# Adapter.net
KiCad netlist of a schematic drawn in Altium Designer
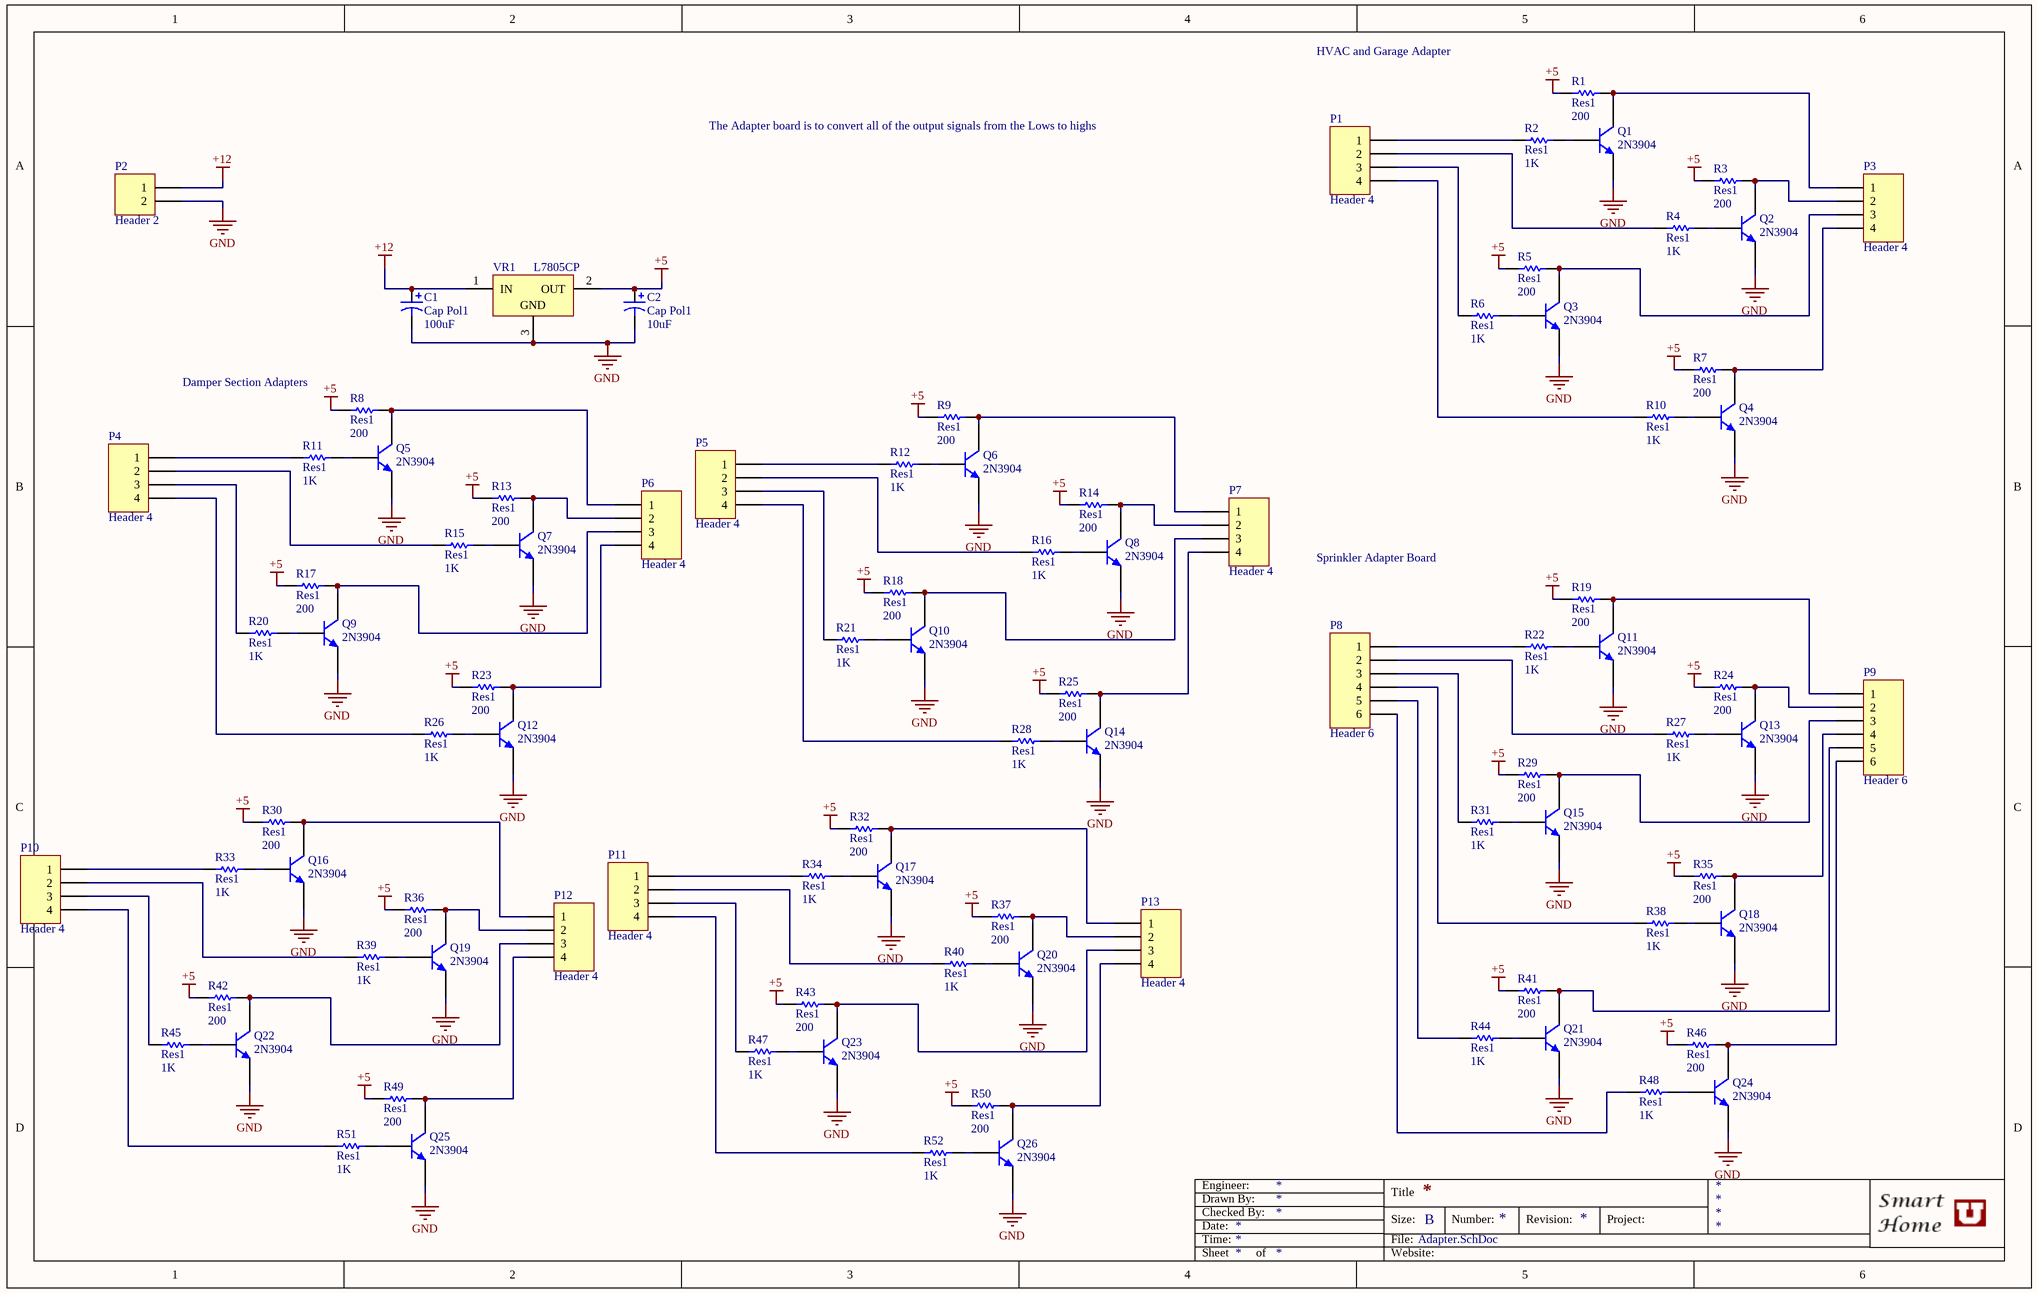
[diagram p0: Adapter.SchDoc]

(export (version "E")
  (design (tool "Eeschema 10.0.6"))
  (components
    (comp (ref "C1")
      (value "Cap Pol1")
      (footprint "RB7.6-15")
      (description "Polarized Capacitor (Radial)")
      (fields (field (name "ALTIUM_VALUE") "100uF") (field (name "PUBLISHER") "Altium Limited"))
      (libsource (lib "Miscellaneous Devices") (part "Cap Pol1"))
    )
    (comp (ref "C2")
      (value "Cap Pol1")
      (footprint "RB7.6-15")
      (description "Polarized Capacitor (Radial)")
      (fields (field (name "ALTIUM_VALUE") "10uF") (field (name "PUBLISHER") "Altium Limited"))
      (libsource (lib "Miscellaneous Devices") (part "Cap Pol1"))
    )
    (comp (ref "P1")
      (value "Header 4")
      (footprint "HDR1X4")
      (description "Header, 4-Pin")
      (fields (field (name "PUBLISHER") "Altium Limited"))
      (libsource (lib "") (part "Header 4_1"))
    )
    (comp (ref "P2")
      (value "Header 2")
      (footprint "HDR1X2")
      (description "Header, 2-Pin")
      (fields (field (name "PUBLISHER") "Altium Limited"))
      (libsource (lib "Miscellaneous Connectors") (part "Header 2"))
    )
    (comp (ref "P3")
      (value "Header 4")
      (footprint "HDR1X4")
      (description "Header, 4-Pin")
      (fields (field (name "PUBLISHER") "Altium Limited"))
      (libsource (lib "Miscellaneous Connectors") (part "Header 4"))
    )
    (comp (ref "P4")
      (value "Header 4")
      (footprint "HDR1X4")
      (description "Header, 4-Pin")
      (fields (field (name "PUBLISHER") "Altium Limited"))
      (libsource (lib "") (part "Header 4_1"))
    )
    (comp (ref "P5")
      (value "Header 4")
      (footprint "HDR1X4")
      (description "Header, 4-Pin")
      (fields (field (name "PUBLISHER") "Altium Limited"))
      (libsource (lib "") (part "Header 4_1"))
    )
    (comp (ref "P6")
      (value "Header 4")
      (footprint "HDR1X4")
      (description "Header, 4-Pin")
      (fields (field (name "PUBLISHER") "Altium Limited"))
      (libsource (lib "Miscellaneous Connectors") (part "Header 4"))
    )
    (comp (ref "P7")
      (value "Header 4")
      (footprint "HDR1X4")
      (description "Header, 4-Pin")
      (fields (field (name "PUBLISHER") "Altium Limited"))
      (libsource (lib "Miscellaneous Connectors") (part "Header 4"))
    )
    (comp (ref "P8")
      (value "Header 6")
      (footprint "HDR1X6")
      (description "Header, 6-Pin")
      (fields (field (name "PUBLISHER") "Altium Limited"))
      (libsource (lib "Miscellaneous Connectors") (part "Header 6"))
    )
    (comp (ref "P9")
      (value "Header 6")
      (footprint "HDR1X6")
      (description "Header, 6-Pin")
      (fields (field (name "PUBLISHER") "Altium Limited"))
      (libsource (lib "") (part "Header 6_1"))
    )
    (comp (ref "P10")
      (value "Header 4")
      (footprint "HDR1X4")
      (description "Header, 4-Pin")
      (fields (field (name "PUBLISHER") "Altium Limited"))
      (libsource (lib "") (part "Header 4_1"))
    )
    (comp (ref "P11")
      (value "Header 4")
      (footprint "HDR1X4")
      (description "Header, 4-Pin")
      (fields (field (name "PUBLISHER") "Altium Limited"))
      (libsource (lib "") (part "Header 4_1"))
    )
    (comp (ref "P12")
      (value "Header 4")
      (footprint "HDR1X4")
      (description "Header, 4-Pin")
      (fields (field (name "PUBLISHER") "Altium Limited"))
      (libsource (lib "Miscellaneous Connectors") (part "Header 4"))
    )
    (comp (ref "P13")
      (value "Header 4")
      (footprint "HDR1X4")
      (description "Header, 4-Pin")
      (fields (field (name "PUBLISHER") "Altium Limited"))
      (libsource (lib "Miscellaneous Connectors") (part "Header 4"))
    )
    (comp (ref "Q1")
      (value "2N3904")
      (footprint "2N3904")
      (description "NPN General Purpose Amplifier")
      (fields (field (name "PUBLISHER") "Altium Limited"))
      (libsource (lib "Miscellaneous Devices") (part "2N3904"))
    )
    (comp (ref "Q2")
      (value "2N3904")
      (footprint "2N3904")
      (description "NPN General Purpose Amplifier")
      (fields (field (name "PUBLISHER") "Altium Limited"))
      (libsource (lib "Miscellaneous Devices") (part "2N3904"))
    )
    (comp (ref "Q3")
      (value "2N3904")
      (footprint "2N3904")
      (description "NPN General Purpose Amplifier")
      (fields (field (name "PUBLISHER") "Altium Limited"))
      (libsource (lib "Miscellaneous Devices") (part "2N3904"))
    )
    (comp (ref "Q4")
      (value "2N3904")
      (footprint "2N3904")
      (description "NPN General Purpose Amplifier")
      (fields (field (name "PUBLISHER") "Altium Limited"))
      (libsource (lib "Miscellaneous Devices") (part "2N3904"))
    )
    (comp (ref "Q5")
      (value "2N3904")
      (footprint "2N3904")
      (description "NPN General Purpose Amplifier")
      (fields (field (name "PUBLISHER") "Altium Limited"))
      (libsource (lib "Miscellaneous Devices") (part "2N3904"))
    )
    (comp (ref "Q6")
      (value "2N3904")
      (footprint "2N3904")
      (description "NPN General Purpose Amplifier")
      (fields (field (name "PUBLISHER") "Altium Limited"))
      (libsource (lib "Miscellaneous Devices") (part "2N3904"))
    )
    (comp (ref "Q7")
      (value "2N3904")
      (footprint "2N3904")
      (description "NPN General Purpose Amplifier")
      (fields (field (name "PUBLISHER") "Altium Limited"))
      (libsource (lib "Miscellaneous Devices") (part "2N3904"))
    )
    (comp (ref "Q8")
      (value "2N3904")
      (footprint "2N3904")
      (description "NPN General Purpose Amplifier")
      (fields (field (name "PUBLISHER") "Altium Limited"))
      (libsource (lib "Miscellaneous Devices") (part "2N3904"))
    )
    (comp (ref "Q9")
      (value "2N3904")
      (footprint "2N3904")
      (description "NPN General Purpose Amplifier")
      (fields (field (name "PUBLISHER") "Altium Limited"))
      (libsource (lib "Miscellaneous Devices") (part "2N3904"))
    )
    (comp (ref "Q10")
      (value "2N3904")
      (footprint "2N3904")
      (description "NPN General Purpose Amplifier")
      (fields (field (name "PUBLISHER") "Altium Limited"))
      (libsource (lib "Miscellaneous Devices") (part "2N3904"))
    )
    (comp (ref "Q11")
      (value "2N3904")
      (footprint "2N3904")
      (description "NPN General Purpose Amplifier")
      (fields (field (name "PUBLISHER") "Altium Limited"))
      (libsource (lib "Miscellaneous Devices") (part "2N3904"))
    )
    (comp (ref "Q12")
      (value "2N3904")
      (footprint "2N3904")
      (description "NPN General Purpose Amplifier")
      (fields (field (name "PUBLISHER") "Altium Limited"))
      (libsource (lib "Miscellaneous Devices") (part "2N3904"))
    )
    (comp (ref "Q13")
      (value "2N3904")
      (footprint "2N3904")
      (description "NPN General Purpose Amplifier")
      (fields (field (name "PUBLISHER") "Altium Limited"))
      (libsource (lib "Miscellaneous Devices") (part "2N3904"))
    )
    (comp (ref "Q14")
      (value "2N3904")
      (footprint "2N3904")
      (description "NPN General Purpose Amplifier")
      (fields (field (name "PUBLISHER") "Altium Limited"))
      (libsource (lib "Miscellaneous Devices") (part "2N3904"))
    )
    (comp (ref "Q15")
      (value "2N3904")
      (footprint "2N3904")
      (description "NPN General Purpose Amplifier")
      (fields (field (name "PUBLISHER") "Altium Limited"))
      (libsource (lib "Miscellaneous Devices") (part "2N3904"))
    )
    (comp (ref "Q16")
      (value "2N3904")
      (footprint "2N3904")
      (description "NPN General Purpose Amplifier")
      (fields (field (name "PUBLISHER") "Altium Limited"))
      (libsource (lib "Miscellaneous Devices") (part "2N3904"))
    )
    (comp (ref "Q17")
      (value "2N3904")
      (footprint "2N3904")
      (description "NPN General Purpose Amplifier")
      (fields (field (name "PUBLISHER") "Altium Limited"))
      (libsource (lib "Miscellaneous Devices") (part "2N3904"))
    )
    (comp (ref "Q18")
      (value "2N3904")
      (footprint "2N3904")
      (description "NPN General Purpose Amplifier")
      (fields (field (name "PUBLISHER") "Altium Limited"))
      (libsource (lib "Miscellaneous Devices") (part "2N3904"))
    )
    (comp (ref "Q19")
      (value "2N3904")
      (footprint "2N3904")
      (description "NPN General Purpose Amplifier")
      (fields (field (name "PUBLISHER") "Altium Limited"))
      (libsource (lib "Miscellaneous Devices") (part "2N3904"))
    )
    (comp (ref "Q20")
      (value "2N3904")
      (footprint "2N3904")
      (description "NPN General Purpose Amplifier")
      (fields (field (name "PUBLISHER") "Altium Limited"))
      (libsource (lib "Miscellaneous Devices") (part "2N3904"))
    )
    (comp (ref "Q21")
      (value "2N3904")
      (footprint "2N3904")
      (description "NPN General Purpose Amplifier")
      (fields (field (name "PUBLISHER") "Altium Limited"))
      (libsource (lib "Miscellaneous Devices") (part "2N3904"))
    )
    (comp (ref "Q22")
      (value "2N3904")
      (footprint "2N3904")
      (description "NPN General Purpose Amplifier")
      (fields (field (name "PUBLISHER") "Altium Limited"))
      (libsource (lib "Miscellaneous Devices") (part "2N3904"))
    )
    (comp (ref "Q23")
      (value "2N3904")
      (footprint "2N3904")
      (description "NPN General Purpose Amplifier")
      (fields (field (name "PUBLISHER") "Altium Limited"))
      (libsource (lib "Miscellaneous Devices") (part "2N3904"))
    )
    (comp (ref "Q24")
      (value "2N3904")
      (footprint "2N3904")
      (description "NPN General Purpose Amplifier")
      (fields (field (name "PUBLISHER") "Altium Limited"))
      (libsource (lib "Miscellaneous Devices") (part "2N3904"))
    )
    (comp (ref "Q25")
      (value "2N3904")
      (footprint "2N3904")
      (description "NPN General Purpose Amplifier")
      (fields (field (name "PUBLISHER") "Altium Limited"))
      (libsource (lib "Miscellaneous Devices") (part "2N3904"))
    )
    (comp (ref "Q26")
      (value "2N3904")
      (footprint "2N3904")
      (description "NPN General Purpose Amplifier")
      (fields (field (name "PUBLISHER") "Altium Limited"))
      (libsource (lib "Miscellaneous Devices") (part "2N3904"))
    )
    (comp (ref "R1")
      (value "Res1")
      (footprint "AXIAL-0.3")
      (description "Resistor")
      (fields (field (name "ALTIUM_VALUE") "200") (field (name "PUBLISHER") "Altium Limited"))
      (libsource (lib "Miscellaneous Devices") (part "Res1"))
    )
    (comp (ref "R2")
      (value "Res1")
      (footprint "AXIAL-0.3")
      (description "Resistor")
      (fields (field (name "ALTIUM_VALUE") "1K") (field (name "PUBLISHER") "Altium Limited"))
      (libsource (lib "Miscellaneous Devices") (part "Res1"))
    )
    (comp (ref "R3")
      (value "Res1")
      (footprint "AXIAL-0.3")
      (description "Resistor")
      (fields (field (name "ALTIUM_VALUE") "200") (field (name "PUBLISHER") "Altium Limited"))
      (libsource (lib "Miscellaneous Devices") (part "Res1"))
    )
    (comp (ref "R4")
      (value "Res1")
      (footprint "AXIAL-0.3")
      (description "Resistor")
      (fields (field (name "ALTIUM_VALUE") "1K") (field (name "PUBLISHER") "Altium Limited"))
      (libsource (lib "Miscellaneous Devices") (part "Res1"))
    )
    (comp (ref "R5")
      (value "Res1")
      (footprint "AXIAL-0.3")
      (description "Resistor")
      (fields (field (name "ALTIUM_VALUE") "200") (field (name "PUBLISHER") "Altium Limited"))
      (libsource (lib "Miscellaneous Devices") (part "Res1"))
    )
    (comp (ref "R6")
      (value "Res1")
      (footprint "AXIAL-0.3")
      (description "Resistor")
      (fields (field (name "ALTIUM_VALUE") "1K") (field (name "PUBLISHER") "Altium Limited"))
      (libsource (lib "Miscellaneous Devices") (part "Res1"))
    )
    (comp (ref "R7")
      (value "Res1")
      (footprint "AXIAL-0.3")
      (description "Resistor")
      (fields (field (name "ALTIUM_VALUE") "200") (field (name "PUBLISHER") "Altium Limited"))
      (libsource (lib "Miscellaneous Devices") (part "Res1"))
    )
    (comp (ref "R8")
      (value "Res1")
      (footprint "AXIAL-0.3")
      (description "Resistor")
      (fields (field (name "ALTIUM_VALUE") "200") (field (name "PUBLISHER") "Altium Limited"))
      (libsource (lib "Miscellaneous Devices") (part "Res1"))
    )
    (comp (ref "R9")
      (value "Res1")
      (footprint "AXIAL-0.3")
      (description "Resistor")
      (fields (field (name "ALTIUM_VALUE") "200") (field (name "PUBLISHER") "Altium Limited"))
      (libsource (lib "Miscellaneous Devices") (part "Res1"))
    )
    (comp (ref "R10")
      (value "Res1")
      (footprint "AXIAL-0.3")
      (description "Resistor")
      (fields (field (name "ALTIUM_VALUE") "1K") (field (name "PUBLISHER") "Altium Limited"))
      (libsource (lib "Miscellaneous Devices") (part "Res1"))
    )
    (comp (ref "R11")
      (value "Res1")
      (footprint "AXIAL-0.3")
      (description "Resistor")
      (fields (field (name "ALTIUM_VALUE") "1K") (field (name "PUBLISHER") "Altium Limited"))
      (libsource (lib "Miscellaneous Devices") (part "Res1"))
    )
    (comp (ref "R12")
      (value "Res1")
      (footprint "AXIAL-0.3")
      (description "Resistor")
      (fields (field (name "ALTIUM_VALUE") "1K") (field (name "PUBLISHER") "Altium Limited"))
      (libsource (lib "Miscellaneous Devices") (part "Res1"))
    )
    (comp (ref "R13")
      (value "Res1")
      (footprint "AXIAL-0.3")
      (description "Resistor")
      (fields (field (name "ALTIUM_VALUE") "200") (field (name "PUBLISHER") "Altium Limited"))
      (libsource (lib "Miscellaneous Devices") (part "Res1"))
    )
    (comp (ref "R14")
      (value "Res1")
      (footprint "AXIAL-0.3")
      (description "Resistor")
      (fields (field (name "ALTIUM_VALUE") "200") (field (name "PUBLISHER") "Altium Limited"))
      (libsource (lib "Miscellaneous Devices") (part "Res1"))
    )
    (comp (ref "R15")
      (value "Res1")
      (footprint "AXIAL-0.3")
      (description "Resistor")
      (fields (field (name "ALTIUM_VALUE") "1K") (field (name "PUBLISHER") "Altium Limited"))
      (libsource (lib "Miscellaneous Devices") (part "Res1"))
    )
    (comp (ref "R16")
      (value "Res1")
      (footprint "AXIAL-0.3")
      (description "Resistor")
      (fields (field (name "ALTIUM_VALUE") "1K") (field (name "PUBLISHER") "Altium Limited"))
      (libsource (lib "Miscellaneous Devices") (part "Res1"))
    )
    (comp (ref "R17")
      (value "Res1")
      (footprint "AXIAL-0.3")
      (description "Resistor")
      (fields (field (name "ALTIUM_VALUE") "200") (field (name "PUBLISHER") "Altium Limited"))
      (libsource (lib "Miscellaneous Devices") (part "Res1"))
    )
    (comp (ref "R18")
      (value "Res1")
      (footprint "AXIAL-0.3")
      (description "Resistor")
      (fields (field (name "ALTIUM_VALUE") "200") (field (name "PUBLISHER") "Altium Limited"))
      (libsource (lib "Miscellaneous Devices") (part "Res1"))
    )
    (comp (ref "R19")
      (value "Res1")
      (footprint "AXIAL-0.3")
      (description "Resistor")
      (fields (field (name "ALTIUM_VALUE") "200") (field (name "PUBLISHER") "Altium Limited"))
      (libsource (lib "Miscellaneous Devices") (part "Res1"))
    )
    (comp (ref "R20")
      (value "Res1")
      (footprint "AXIAL-0.3")
      (description "Resistor")
      (fields (field (name "ALTIUM_VALUE") "1K") (field (name "PUBLISHER") "Altium Limited"))
      (libsource (lib "Miscellaneous Devices") (part "Res1"))
    )
    (comp (ref "R21")
      (value "Res1")
      (footprint "AXIAL-0.3")
      (description "Resistor")
      (fields (field (name "ALTIUM_VALUE") "1K") (field (name "PUBLISHER") "Altium Limited"))
      (libsource (lib "Miscellaneous Devices") (part "Res1"))
    )
    (comp (ref "R22")
      (value "Res1")
      (footprint "AXIAL-0.3")
      (description "Resistor")
      (fields (field (name "ALTIUM_VALUE") "1K") (field (name "PUBLISHER") "Altium Limited"))
      (libsource (lib "Miscellaneous Devices") (part "Res1"))
    )
    (comp (ref "R23")
      (value "Res1")
      (footprint "AXIAL-0.3")
      (description "Resistor")
      (fields (field (name "ALTIUM_VALUE") "200") (field (name "PUBLISHER") "Altium Limited"))
      (libsource (lib "Miscellaneous Devices") (part "Res1"))
    )
    (comp (ref "R24")
      (value "Res1")
      (footprint "AXIAL-0.3")
      (description "Resistor")
      (fields (field (name "ALTIUM_VALUE") "200") (field (name "PUBLISHER") "Altium Limited"))
      (libsource (lib "Miscellaneous Devices") (part "Res1"))
    )
    (comp (ref "R25")
      (value "Res1")
      (footprint "AXIAL-0.3")
      (description "Resistor")
      (fields (field (name "ALTIUM_VALUE") "200") (field (name "PUBLISHER") "Altium Limited"))
      (libsource (lib "Miscellaneous Devices") (part "Res1"))
    )
    (comp (ref "R26")
      (value "Res1")
      (footprint "AXIAL-0.3")
      (description "Resistor")
      (fields (field (name "ALTIUM_VALUE") "1K") (field (name "PUBLISHER") "Altium Limited"))
      (libsource (lib "Miscellaneous Devices") (part "Res1"))
    )
    (comp (ref "R27")
      (value "Res1")
      (footprint "AXIAL-0.3")
      (description "Resistor")
      (fields (field (name "ALTIUM_VALUE") "1K") (field (name "PUBLISHER") "Altium Limited"))
      (libsource (lib "Miscellaneous Devices") (part "Res1"))
    )
    (comp (ref "R28")
      (value "Res1")
      (footprint "AXIAL-0.3")
      (description "Resistor")
      (fields (field (name "ALTIUM_VALUE") "1K") (field (name "PUBLISHER") "Altium Limited"))
      (libsource (lib "Miscellaneous Devices") (part "Res1"))
    )
    (comp (ref "R29")
      (value "Res1")
      (footprint "AXIAL-0.3")
      (description "Resistor")
      (fields (field (name "ALTIUM_VALUE") "200") (field (name "PUBLISHER") "Altium Limited"))
      (libsource (lib "Miscellaneous Devices") (part "Res1"))
    )
    (comp (ref "R30")
      (value "Res1")
      (footprint "AXIAL-0.3")
      (description "Resistor")
      (fields (field (name "ALTIUM_VALUE") "200") (field (name "PUBLISHER") "Altium Limited"))
      (libsource (lib "Miscellaneous Devices") (part "Res1"))
    )
    (comp (ref "R31")
      (value "Res1")
      (footprint "AXIAL-0.3")
      (description "Resistor")
      (fields (field (name "ALTIUM_VALUE") "1K") (field (name "PUBLISHER") "Altium Limited"))
      (libsource (lib "Miscellaneous Devices") (part "Res1"))
    )
    (comp (ref "R32")
      (value "Res1")
      (footprint "AXIAL-0.3")
      (description "Resistor")
      (fields (field (name "ALTIUM_VALUE") "200") (field (name "PUBLISHER") "Altium Limited"))
      (libsource (lib "Miscellaneous Devices") (part "Res1"))
    )
    (comp (ref "R33")
      (value "Res1")
      (footprint "AXIAL-0.3")
      (description "Resistor")
      (fields (field (name "ALTIUM_VALUE") "1K") (field (name "PUBLISHER") "Altium Limited"))
      (libsource (lib "Miscellaneous Devices") (part "Res1"))
    )
    (comp (ref "R34")
      (value "Res1")
      (footprint "AXIAL-0.3")
      (description "Resistor")
      (fields (field (name "ALTIUM_VALUE") "1K") (field (name "PUBLISHER") "Altium Limited"))
      (libsource (lib "Miscellaneous Devices") (part "Res1"))
    )
    (comp (ref "R35")
      (value "Res1")
      (footprint "AXIAL-0.3")
      (description "Resistor")
      (fields (field (name "ALTIUM_VALUE") "200") (field (name "PUBLISHER") "Altium Limited"))
      (libsource (lib "Miscellaneous Devices") (part "Res1"))
    )
    (comp (ref "R36")
      (value "Res1")
      (footprint "AXIAL-0.3")
      (description "Resistor")
      (fields (field (name "ALTIUM_VALUE") "200") (field (name "PUBLISHER") "Altium Limited"))
      (libsource (lib "Miscellaneous Devices") (part "Res1"))
    )
    (comp (ref "R37")
      (value "Res1")
      (footprint "AXIAL-0.3")
      (description "Resistor")
      (fields (field (name "ALTIUM_VALUE") "200") (field (name "PUBLISHER") "Altium Limited"))
      (libsource (lib "Miscellaneous Devices") (part "Res1"))
    )
    (comp (ref "R38")
      (value "Res1")
      (footprint "AXIAL-0.3")
      (description "Resistor")
      (fields (field (name "ALTIUM_VALUE") "1K") (field (name "PUBLISHER") "Altium Limited"))
      (libsource (lib "Miscellaneous Devices") (part "Res1"))
    )
    (comp (ref "R39")
      (value "Res1")
      (footprint "AXIAL-0.3")
      (description "Resistor")
      (fields (field (name "ALTIUM_VALUE") "1K") (field (name "PUBLISHER") "Altium Limited"))
      (libsource (lib "Miscellaneous Devices") (part "Res1"))
    )
    (comp (ref "R40")
      (value "Res1")
      (footprint "AXIAL-0.3")
      (description "Resistor")
      (fields (field (name "ALTIUM_VALUE") "1K") (field (name "PUBLISHER") "Altium Limited"))
      (libsource (lib "Miscellaneous Devices") (part "Res1"))
    )
    (comp (ref "R41")
      (value "Res1")
      (footprint "AXIAL-0.3")
      (description "Resistor")
      (fields (field (name "ALTIUM_VALUE") "200") (field (name "PUBLISHER") "Altium Limited"))
      (libsource (lib "Miscellaneous Devices") (part "Res1"))
    )
    (comp (ref "R42")
      (value "Res1")
      (footprint "AXIAL-0.3")
      (description "Resistor")
      (fields (field (name "ALTIUM_VALUE") "200") (field (name "PUBLISHER") "Altium Limited"))
      (libsource (lib "Miscellaneous Devices") (part "Res1"))
    )
    (comp (ref "R43")
      (value "Res1")
      (footprint "AXIAL-0.3")
      (description "Resistor")
      (fields (field (name "ALTIUM_VALUE") "200") (field (name "PUBLISHER") "Altium Limited"))
      (libsource (lib "Miscellaneous Devices") (part "Res1"))
    )
    (comp (ref "R44")
      (value "Res1")
      (footprint "AXIAL-0.3")
      (description "Resistor")
      (fields (field (name "ALTIUM_VALUE") "1K") (field (name "PUBLISHER") "Altium Limited"))
      (libsource (lib "Miscellaneous Devices") (part "Res1"))
    )
    (comp (ref "R45")
      (value "Res1")
      (footprint "AXIAL-0.3")
      (description "Resistor")
      (fields (field (name "ALTIUM_VALUE") "1K") (field (name "PUBLISHER") "Altium Limited"))
      (libsource (lib "Miscellaneous Devices") (part "Res1"))
    )
    (comp (ref "R46")
      (value "Res1")
      (footprint "AXIAL-0.3")
      (description "Resistor")
      (fields (field (name "ALTIUM_VALUE") "200") (field (name "PUBLISHER") "Altium Limited"))
      (libsource (lib "Miscellaneous Devices") (part "Res1"))
    )
    (comp (ref "R47")
      (value "Res1")
      (footprint "AXIAL-0.3")
      (description "Resistor")
      (fields (field (name "ALTIUM_VALUE") "1K") (field (name "PUBLISHER") "Altium Limited"))
      (libsource (lib "Miscellaneous Devices") (part "Res1"))
    )
    (comp (ref "R48")
      (value "Res1")
      (footprint "AXIAL-0.3")
      (description "Resistor")
      (fields (field (name "ALTIUM_VALUE") "1K") (field (name "PUBLISHER") "Altium Limited"))
      (libsource (lib "Miscellaneous Devices") (part "Res1"))
    )
    (comp (ref "R49")
      (value "Res1")
      (footprint "AXIAL-0.3")
      (description "Resistor")
      (fields (field (name "ALTIUM_VALUE") "200") (field (name "PUBLISHER") "Altium Limited"))
      (libsource (lib "Miscellaneous Devices") (part "Res1"))
    )
    (comp (ref "R50")
      (value "Res1")
      (footprint "AXIAL-0.3")
      (description "Resistor")
      (fields (field (name "ALTIUM_VALUE") "200") (field (name "PUBLISHER") "Altium Limited"))
      (libsource (lib "Miscellaneous Devices") (part "Res1"))
    )
    (comp (ref "R51")
      (value "Res1")
      (footprint "AXIAL-0.3")
      (description "Resistor")
      (fields (field (name "ALTIUM_VALUE") "1K") (field (name "PUBLISHER") "Altium Limited"))
      (libsource (lib "Miscellaneous Devices") (part "Res1"))
    )
    (comp (ref "R52")
      (value "Res1")
      (footprint "AXIAL-0.3")
      (description "Resistor")
      (fields (field (name "ALTIUM_VALUE") "1K") (field (name "PUBLISHER") "Altium Limited"))
      (libsource (lib "Miscellaneous Devices") (part "Res1"))
    )
    (comp (ref "VR1")
      (value "L7805CP")
      (footprint "ISOWATT220AB")
      (description "Positive Voltage Regulator")
      (fields (field (name "PUBLISHER") "Altium Limited"))
      (libsource (lib "ST Power Mgt Voltage Regulator") (part "L7805CP"))
    )
  )
  (nets
    (net (code "1") (name "+5") (class "Default")
      (node (ref "C2") (pin "1") (pinfunction "1_1") (pintype "passive"))
      (node (ref "R1") (pin "1") (pinfunction "1_1") (pintype "passive"))
      (node (ref "R13") (pin "1") (pinfunction "1_1") (pintype "passive"))
      (node (ref "R14") (pin "1") (pinfunction "1_1") (pintype "passive"))
      (node (ref "R17") (pin "1") (pinfunction "1_1") (pintype "passive"))
      (node (ref "R18") (pin "1") (pinfunction "1_1") (pintype "passive"))
      (node (ref "R19") (pin "1") (pinfunction "1_1") (pintype "passive"))
      (node (ref "R23") (pin "1") (pinfunction "1_1") (pintype "passive"))
      (node (ref "R24") (pin "1") (pinfunction "1_1") (pintype "passive"))
      (node (ref "R25") (pin "1") (pinfunction "1_1") (pintype "passive"))
      (node (ref "R29") (pin "1") (pinfunction "1_1") (pintype "passive"))
      (node (ref "R3") (pin "1") (pinfunction "1_1") (pintype "passive"))
      (node (ref "R30") (pin "1") (pinfunction "1_1") (pintype "passive"))
      (node (ref "R32") (pin "1") (pinfunction "1_1") (pintype "passive"))
      (node (ref "R35") (pin "1") (pinfunction "1_1") (pintype "passive"))
      (node (ref "R36") (pin "1") (pinfunction "1_1") (pintype "passive"))
      (node (ref "R37") (pin "1") (pinfunction "1_1") (pintype "passive"))
      (node (ref "R41") (pin "1") (pinfunction "1_1") (pintype "passive"))
      (node (ref "R42") (pin "1") (pinfunction "1_1") (pintype "passive"))
      (node (ref "R43") (pin "1") (pinfunction "1_1") (pintype "passive"))
      (node (ref "R46") (pin "1") (pinfunction "1_1") (pintype "passive"))
      (node (ref "R49") (pin "1") (pinfunction "1_1") (pintype "passive"))
      (node (ref "R5") (pin "1") (pinfunction "1_1") (pintype "passive"))
      (node (ref "R50") (pin "1") (pinfunction "1_1") (pintype "passive"))
      (node (ref "R7") (pin "1") (pinfunction "1_1") (pintype "passive"))
      (node (ref "R8") (pin "1") (pinfunction "1_1") (pintype "passive"))
      (node (ref "R9") (pin "1") (pinfunction "1_1") (pintype "passive"))
      (node (ref "VR1") (pin "2") (pinfunction "OUT_2") (pintype "power_in"))
    )
    (net (code "2") (name "+12") (class "Default")
      (node (ref "C1") (pin "1") (pinfunction "1_1") (pintype "passive"))
      (node (ref "P2") (pin "1") (pinfunction "1_1") (pintype "passive"))
      (node (ref "VR1") (pin "1") (pinfunction "IN_1") (pintype "power_in"))
    )
    (net (code "3") (name "GND") (class "Default")
      (node (ref "C1") (pin "2") (pinfunction "2_2") (pintype "passive"))
      (node (ref "C2") (pin "2") (pinfunction "2_2") (pintype "passive"))
      (node (ref "P2") (pin "2") (pinfunction "2_2") (pintype "passive"))
      (node (ref "Q1") (pin "1") (pinfunction "E_1") (pintype "passive"))
      (node (ref "Q10") (pin "1") (pinfunction "E_1") (pintype "passive"))
      (node (ref "Q11") (pin "1") (pinfunction "E_1") (pintype "passive"))
      (node (ref "Q12") (pin "1") (pinfunction "E_1") (pintype "passive"))
      (node (ref "Q13") (pin "1") (pinfunction "E_1") (pintype "passive"))
      (node (ref "Q14") (pin "1") (pinfunction "E_1") (pintype "passive"))
      (node (ref "Q15") (pin "1") (pinfunction "E_1") (pintype "passive"))
      (node (ref "Q16") (pin "1") (pinfunction "E_1") (pintype "passive"))
      (node (ref "Q17") (pin "1") (pinfunction "E_1") (pintype "passive"))
      (node (ref "Q18") (pin "1") (pinfunction "E_1") (pintype "passive"))
      (node (ref "Q19") (pin "1") (pinfunction "E_1") (pintype "passive"))
      (node (ref "Q2") (pin "1") (pinfunction "E_1") (pintype "passive"))
      (node (ref "Q20") (pin "1") (pinfunction "E_1") (pintype "passive"))
      (node (ref "Q21") (pin "1") (pinfunction "E_1") (pintype "passive"))
      (node (ref "Q22") (pin "1") (pinfunction "E_1") (pintype "passive"))
      (node (ref "Q23") (pin "1") (pinfunction "E_1") (pintype "passive"))
      (node (ref "Q24") (pin "1") (pinfunction "E_1") (pintype "passive"))
      (node (ref "Q25") (pin "1") (pinfunction "E_1") (pintype "passive"))
      (node (ref "Q26") (pin "1") (pinfunction "E_1") (pintype "passive"))
      (node (ref "Q3") (pin "1") (pinfunction "E_1") (pintype "passive"))
      (node (ref "Q4") (pin "1") (pinfunction "E_1") (pintype "passive"))
      (node (ref "Q5") (pin "1") (pinfunction "E_1") (pintype "passive"))
      (node (ref "Q6") (pin "1") (pinfunction "E_1") (pintype "passive"))
      (node (ref "Q7") (pin "1") (pinfunction "E_1") (pintype "passive"))
      (node (ref "Q8") (pin "1") (pinfunction "E_1") (pintype "passive"))
      (node (ref "Q9") (pin "1") (pinfunction "E_1") (pintype "passive"))
      (node (ref "VR1") (pin "3") (pinfunction "GND_3") (pintype "power_in"))
    )
    (net (code "4") (name "Net-(P1-Pad1)") (class "Default")
      (node (ref "P1") (pin "1") (pinfunction "1_1") (pintype "passive"))
      (node (ref "R2") (pin "1") (pinfunction "1_1") (pintype "passive"))
    )
    (net (code "5") (name "Net-(P1-Pad2)") (class "Default")
      (node (ref "P1") (pin "2") (pinfunction "2_2") (pintype "passive"))
      (node (ref "R4") (pin "1") (pinfunction "1_1") (pintype "passive"))
    )
    (net (code "6") (name "Net-(P1-Pad3)") (class "Default")
      (node (ref "P1") (pin "3") (pinfunction "3_3") (pintype "passive"))
      (node (ref "R6") (pin "1") (pinfunction "1_1") (pintype "passive"))
    )
    (net (code "7") (name "Net-(P1-Pad4)") (class "Default")
      (node (ref "P1") (pin "4") (pinfunction "4_4") (pintype "passive"))
      (node (ref "R10") (pin "1") (pinfunction "1_1") (pintype "passive"))
    )
    (net (code "8") (name "Net-(P4-Pad1)") (class "Default")
      (node (ref "P4") (pin "1") (pinfunction "1_1") (pintype "passive"))
      (node (ref "R11") (pin "1") (pinfunction "1_1") (pintype "passive"))
    )
    (net (code "9") (name "Net-(P4-Pad2)") (class "Default")
      (node (ref "P4") (pin "2") (pinfunction "2_2") (pintype "passive"))
      (node (ref "R15") (pin "1") (pinfunction "1_1") (pintype "passive"))
    )
    (net (code "10") (name "Net-(P4-Pad3)") (class "Default")
      (node (ref "P4") (pin "3") (pinfunction "3_3") (pintype "passive"))
      (node (ref "R20") (pin "1") (pinfunction "1_1") (pintype "passive"))
    )
    (net (code "11") (name "Net-(P4-Pad4)") (class "Default")
      (node (ref "P4") (pin "4") (pinfunction "4_4") (pintype "passive"))
      (node (ref "R26") (pin "1") (pinfunction "1_1") (pintype "passive"))
    )
    (net (code "12") (name "Net-(P5-Pad1)") (class "Default")
      (node (ref "P5") (pin "1") (pinfunction "1_1") (pintype "passive"))
      (node (ref "R12") (pin "1") (pinfunction "1_1") (pintype "passive"))
    )
    (net (code "13") (name "Net-(P5-Pad2)") (class "Default")
      (node (ref "P5") (pin "2") (pinfunction "2_2") (pintype "passive"))
      (node (ref "R16") (pin "1") (pinfunction "1_1") (pintype "passive"))
    )
    (net (code "14") (name "Net-(P5-Pad3)") (class "Default")
      (node (ref "P5") (pin "3") (pinfunction "3_3") (pintype "passive"))
      (node (ref "R21") (pin "1") (pinfunction "1_1") (pintype "passive"))
    )
    (net (code "15") (name "Net-(P5-Pad4)") (class "Default")
      (node (ref "P5") (pin "4") (pinfunction "4_4") (pintype "passive"))
      (node (ref "R28") (pin "1") (pinfunction "1_1") (pintype "passive"))
    )
    (net (code "16") (name "Net-(P8-Pad1)") (class "Default")
      (node (ref "P8") (pin "1") (pinfunction "1_1") (pintype "passive"))
      (node (ref "R22") (pin "1") (pinfunction "1_1") (pintype "passive"))
    )
    (net (code "17") (name "Net-(P8-Pad2)") (class "Default")
      (node (ref "P8") (pin "2") (pinfunction "2_2") (pintype "passive"))
      (node (ref "R27") (pin "1") (pinfunction "1_1") (pintype "passive"))
    )
    (net (code "18") (name "Net-(P8-Pad3)") (class "Default")
      (node (ref "P8") (pin "3") (pinfunction "3_3") (pintype "passive"))
      (node (ref "R31") (pin "1") (pinfunction "1_1") (pintype "passive"))
    )
    (net (code "19") (name "Net-(P8-Pad4)") (class "Default")
      (node (ref "P8") (pin "4") (pinfunction "4_4") (pintype "passive"))
      (node (ref "R38") (pin "1") (pinfunction "1_1") (pintype "passive"))
    )
    (net (code "20") (name "Net-(P8-Pad5)") (class "Default")
      (node (ref "P8") (pin "5") (pinfunction "5_5") (pintype "passive"))
      (node (ref "R44") (pin "1") (pinfunction "1_1") (pintype "passive"))
    )
    (net (code "21") (name "Net-(P8-Pad6)") (class "Default")
      (node (ref "P8") (pin "6") (pinfunction "6_6") (pintype "passive"))
      (node (ref "R48") (pin "1") (pinfunction "1_1") (pintype "passive"))
    )
    (net (code "22") (name "Net-(P10-Pad1)") (class "Default")
      (node (ref "P10") (pin "1") (pinfunction "1_1") (pintype "passive"))
      (node (ref "R33") (pin "1") (pinfunction "1_1") (pintype "passive"))
    )
    (net (code "23") (name "Net-(P10-Pad2)") (class "Default")
      (node (ref "P10") (pin "2") (pinfunction "2_2") (pintype "passive"))
      (node (ref "R39") (pin "1") (pinfunction "1_1") (pintype "passive"))
    )
    (net (code "24") (name "Net-(P10-Pad3)") (class "Default")
      (node (ref "P10") (pin "3") (pinfunction "3_3") (pintype "passive"))
      (node (ref "R45") (pin "1") (pinfunction "1_1") (pintype "passive"))
    )
    (net (code "25") (name "Net-(P10-Pad4)") (class "Default")
      (node (ref "P10") (pin "4") (pinfunction "4_4") (pintype "passive"))
      (node (ref "R51") (pin "1") (pinfunction "1_1") (pintype "passive"))
    )
    (net (code "26") (name "Net-(P11-Pad1)") (class "Default")
      (node (ref "P11") (pin "1") (pinfunction "1_1") (pintype "passive"))
      (node (ref "R34") (pin "1") (pinfunction "1_1") (pintype "passive"))
    )
    (net (code "27") (name "Net-(P11-Pad2)") (class "Default")
      (node (ref "P11") (pin "2") (pinfunction "2_2") (pintype "passive"))
      (node (ref "R40") (pin "1") (pinfunction "1_1") (pintype "passive"))
    )
    (net (code "28") (name "Net-(P11-Pad3)") (class "Default")
      (node (ref "P11") (pin "3") (pinfunction "3_3") (pintype "passive"))
      (node (ref "R47") (pin "1") (pinfunction "1_1") (pintype "passive"))
    )
    (net (code "29") (name "Net-(P11-Pad4)") (class "Default")
      (node (ref "P11") (pin "4") (pinfunction "4_4") (pintype "passive"))
      (node (ref "R52") (pin "1") (pinfunction "1_1") (pintype "passive"))
    )
    (net (code "30") (name "Net-(Q1-B)") (class "Default")
      (node (ref "Q1") (pin "2") (pinfunction "B_2") (pintype "passive"))
      (node (ref "R2") (pin "2") (pinfunction "2_2") (pintype "passive"))
    )
    (net (code "31") (name "Net-(Q1-C)") (class "Default")
      (node (ref "P3") (pin "1") (pinfunction "1_1") (pintype "passive"))
      (node (ref "Q1") (pin "3") (pinfunction "C_3") (pintype "passive"))
      (node (ref "R1") (pin "2") (pinfunction "2_2") (pintype "passive"))
    )
    (net (code "32") (name "Net-(Q2-B)") (class "Default")
      (node (ref "Q2") (pin "2") (pinfunction "B_2") (pintype "passive"))
      (node (ref "R4") (pin "2") (pinfunction "2_2") (pintype "passive"))
    )
    (net (code "33") (name "Net-(Q2-C)") (class "Default")
      (node (ref "P3") (pin "2") (pinfunction "2_2") (pintype "passive"))
      (node (ref "Q2") (pin "3") (pinfunction "C_3") (pintype "passive"))
      (node (ref "R3") (pin "2") (pinfunction "2_2") (pintype "passive"))
    )
    (net (code "34") (name "Net-(Q3-B)") (class "Default")
      (node (ref "Q3") (pin "2") (pinfunction "B_2") (pintype "passive"))
      (node (ref "R6") (pin "2") (pinfunction "2_2") (pintype "passive"))
    )
    (net (code "35") (name "Net-(Q3-C)") (class "Default")
      (node (ref "P3") (pin "3") (pinfunction "3_3") (pintype "passive"))
      (node (ref "Q3") (pin "3") (pinfunction "C_3") (pintype "passive"))
      (node (ref "R5") (pin "2") (pinfunction "2_2") (pintype "passive"))
    )
    (net (code "36") (name "Net-(Q4-B)") (class "Default")
      (node (ref "Q4") (pin "2") (pinfunction "B_2") (pintype "passive"))
      (node (ref "R10") (pin "2") (pinfunction "2_2") (pintype "passive"))
    )
    (net (code "37") (name "Net-(Q4-C)") (class "Default")
      (node (ref "P3") (pin "4") (pinfunction "4_4") (pintype "passive"))
      (node (ref "Q4") (pin "3") (pinfunction "C_3") (pintype "passive"))
      (node (ref "R7") (pin "2") (pinfunction "2_2") (pintype "passive"))
    )
    (net (code "38") (name "Net-(Q5-B)") (class "Default")
      (node (ref "Q5") (pin "2") (pinfunction "B_2") (pintype "passive"))
      (node (ref "R11") (pin "2") (pinfunction "2_2") (pintype "passive"))
    )
    (net (code "39") (name "Net-(Q5-C)") (class "Default")
      (node (ref "P6") (pin "1") (pinfunction "1_1") (pintype "passive"))
      (node (ref "Q5") (pin "3") (pinfunction "C_3") (pintype "passive"))
      (node (ref "R8") (pin "2") (pinfunction "2_2") (pintype "passive"))
    )
    (net (code "40") (name "Net-(Q6-B)") (class "Default")
      (node (ref "Q6") (pin "2") (pinfunction "B_2") (pintype "passive"))
      (node (ref "R12") (pin "2") (pinfunction "2_2") (pintype "passive"))
    )
    (net (code "41") (name "Net-(Q6-C)") (class "Default")
      (node (ref "P7") (pin "1") (pinfunction "1_1") (pintype "passive"))
      (node (ref "Q6") (pin "3") (pinfunction "C_3") (pintype "passive"))
      (node (ref "R9") (pin "2") (pinfunction "2_2") (pintype "passive"))
    )
    (net (code "42") (name "Net-(Q7-B)") (class "Default")
      (node (ref "Q7") (pin "2") (pinfunction "B_2") (pintype "passive"))
      (node (ref "R15") (pin "2") (pinfunction "2_2") (pintype "passive"))
    )
    (net (code "43") (name "Net-(Q7-C)") (class "Default")
      (node (ref "P6") (pin "2") (pinfunction "2_2") (pintype "passive"))
      (node (ref "Q7") (pin "3") (pinfunction "C_3") (pintype "passive"))
      (node (ref "R13") (pin "2") (pinfunction "2_2") (pintype "passive"))
    )
    (net (code "44") (name "Net-(Q8-B)") (class "Default")
      (node (ref "Q8") (pin "2") (pinfunction "B_2") (pintype "passive"))
      (node (ref "R16") (pin "2") (pinfunction "2_2") (pintype "passive"))
    )
    (net (code "45") (name "Net-(Q8-C)") (class "Default")
      (node (ref "P7") (pin "2") (pinfunction "2_2") (pintype "passive"))
      (node (ref "Q8") (pin "3") (pinfunction "C_3") (pintype "passive"))
      (node (ref "R14") (pin "2") (pinfunction "2_2") (pintype "passive"))
    )
    (net (code "46") (name "Net-(Q9-B)") (class "Default")
      (node (ref "Q9") (pin "2") (pinfunction "B_2") (pintype "passive"))
      (node (ref "R20") (pin "2") (pinfunction "2_2") (pintype "passive"))
    )
    (net (code "47") (name "Net-(Q9-C)") (class "Default")
      (node (ref "P6") (pin "3") (pinfunction "3_3") (pintype "passive"))
      (node (ref "Q9") (pin "3") (pinfunction "C_3") (pintype "passive"))
      (node (ref "R17") (pin "2") (pinfunction "2_2") (pintype "passive"))
    )
    (net (code "48") (name "Net-(Q10-B)") (class "Default")
      (node (ref "Q10") (pin "2") (pinfunction "B_2") (pintype "passive"))
      (node (ref "R21") (pin "2") (pinfunction "2_2") (pintype "passive"))
    )
    (net (code "49") (name "Net-(Q10-C)") (class "Default")
      (node (ref "P7") (pin "3") (pinfunction "3_3") (pintype "passive"))
      (node (ref "Q10") (pin "3") (pinfunction "C_3") (pintype "passive"))
      (node (ref "R18") (pin "2") (pinfunction "2_2") (pintype "passive"))
    )
    (net (code "50") (name "Net-(Q11-B)") (class "Default")
      (node (ref "Q11") (pin "2") (pinfunction "B_2") (pintype "passive"))
      (node (ref "R22") (pin "2") (pinfunction "2_2") (pintype "passive"))
    )
    (net (code "51") (name "Net-(Q11-C)") (class "Default")
      (node (ref "P9") (pin "1") (pinfunction "1_1") (pintype "passive"))
      (node (ref "Q11") (pin "3") (pinfunction "C_3") (pintype "passive"))
      (node (ref "R19") (pin "2") (pinfunction "2_2") (pintype "passive"))
    )
    (net (code "52") (name "Net-(Q12-B)") (class "Default")
      (node (ref "Q12") (pin "2") (pinfunction "B_2") (pintype "passive"))
      (node (ref "R26") (pin "2") (pinfunction "2_2") (pintype "passive"))
    )
    (net (code "53") (name "Net-(Q12-C)") (class "Default")
      (node (ref "P6") (pin "4") (pinfunction "4_4") (pintype "passive"))
      (node (ref "Q12") (pin "3") (pinfunction "C_3") (pintype "passive"))
      (node (ref "R23") (pin "2") (pinfunction "2_2") (pintype "passive"))
    )
    (net (code "54") (name "Net-(Q13-B)") (class "Default")
      (node (ref "Q13") (pin "2") (pinfunction "B_2") (pintype "passive"))
      (node (ref "R27") (pin "2") (pinfunction "2_2") (pintype "passive"))
    )
    (net (code "55") (name "Net-(Q13-C)") (class "Default")
      (node (ref "P9") (pin "2") (pinfunction "2_2") (pintype "passive"))
      (node (ref "Q13") (pin "3") (pinfunction "C_3") (pintype "passive"))
      (node (ref "R24") (pin "2") (pinfunction "2_2") (pintype "passive"))
    )
    (net (code "56") (name "Net-(Q14-B)") (class "Default")
      (node (ref "Q14") (pin "2") (pinfunction "B_2") (pintype "passive"))
      (node (ref "R28") (pin "2") (pinfunction "2_2") (pintype "passive"))
    )
    (net (code "57") (name "Net-(Q14-C)") (class "Default")
      (node (ref "P7") (pin "4") (pinfunction "4_4") (pintype "passive"))
      (node (ref "Q14") (pin "3") (pinfunction "C_3") (pintype "passive"))
      (node (ref "R25") (pin "2") (pinfunction "2_2") (pintype "passive"))
    )
    (net (code "58") (name "Net-(Q15-B)") (class "Default")
      (node (ref "Q15") (pin "2") (pinfunction "B_2") (pintype "passive"))
      (node (ref "R31") (pin "2") (pinfunction "2_2") (pintype "passive"))
    )
    (net (code "59") (name "Net-(Q15-C)") (class "Default")
      (node (ref "P9") (pin "3") (pinfunction "3_3") (pintype "passive"))
      (node (ref "Q15") (pin "3") (pinfunction "C_3") (pintype "passive"))
      (node (ref "R29") (pin "2") (pinfunction "2_2") (pintype "passive"))
    )
    (net (code "60") (name "Net-(Q16-B)") (class "Default")
      (node (ref "Q16") (pin "2") (pinfunction "B_2") (pintype "passive"))
      (node (ref "R33") (pin "2") (pinfunction "2_2") (pintype "passive"))
    )
    (net (code "61") (name "Net-(Q16-C)") (class "Default")
      (node (ref "P12") (pin "1") (pinfunction "1_1") (pintype "passive"))
      (node (ref "Q16") (pin "3") (pinfunction "C_3") (pintype "passive"))
      (node (ref "R30") (pin "2") (pinfunction "2_2") (pintype "passive"))
    )
    (net (code "62") (name "Net-(Q17-B)") (class "Default")
      (node (ref "Q17") (pin "2") (pinfunction "B_2") (pintype "passive"))
      (node (ref "R34") (pin "2") (pinfunction "2_2") (pintype "passive"))
    )
    (net (code "63") (name "Net-(Q17-C)") (class "Default")
      (node (ref "P13") (pin "1") (pinfunction "1_1") (pintype "passive"))
      (node (ref "Q17") (pin "3") (pinfunction "C_3") (pintype "passive"))
      (node (ref "R32") (pin "2") (pinfunction "2_2") (pintype "passive"))
    )
    (net (code "64") (name "Net-(Q18-B)") (class "Default")
      (node (ref "Q18") (pin "2") (pinfunction "B_2") (pintype "passive"))
      (node (ref "R38") (pin "2") (pinfunction "2_2") (pintype "passive"))
    )
    (net (code "65") (name "Net-(Q18-C)") (class "Default")
      (node (ref "P9") (pin "4") (pinfunction "4_4") (pintype "passive"))
      (node (ref "Q18") (pin "3") (pinfunction "C_3") (pintype "passive"))
      (node (ref "R35") (pin "2") (pinfunction "2_2") (pintype "passive"))
    )
    (net (code "66") (name "Net-(Q19-B)") (class "Default")
      (node (ref "Q19") (pin "2") (pinfunction "B_2") (pintype "passive"))
      (node (ref "R39") (pin "2") (pinfunction "2_2") (pintype "passive"))
    )
    (net (code "67") (name "Net-(Q19-C)") (class "Default")
      (node (ref "P12") (pin "2") (pinfunction "2_2") (pintype "passive"))
      (node (ref "Q19") (pin "3") (pinfunction "C_3") (pintype "passive"))
      (node (ref "R36") (pin "2") (pinfunction "2_2") (pintype "passive"))
    )
    (net (code "68") (name "Net-(Q20-B)") (class "Default")
      (node (ref "Q20") (pin "2") (pinfunction "B_2") (pintype "passive"))
      (node (ref "R40") (pin "2") (pinfunction "2_2") (pintype "passive"))
    )
    (net (code "69") (name "Net-(Q20-C)") (class "Default")
      (node (ref "P13") (pin "2") (pinfunction "2_2") (pintype "passive"))
      (node (ref "Q20") (pin "3") (pinfunction "C_3") (pintype "passive"))
      (node (ref "R37") (pin "2") (pinfunction "2_2") (pintype "passive"))
    )
    (net (code "70") (name "Net-(Q21-B)") (class "Default")
      (node (ref "Q21") (pin "2") (pinfunction "B_2") (pintype "passive"))
      (node (ref "R44") (pin "2") (pinfunction "2_2") (pintype "passive"))
    )
    (net (code "71") (name "Net-(Q21-C)") (class "Default")
      (node (ref "P9") (pin "5") (pinfunction "5_5") (pintype "passive"))
      (node (ref "Q21") (pin "3") (pinfunction "C_3") (pintype "passive"))
      (node (ref "R41") (pin "2") (pinfunction "2_2") (pintype "passive"))
    )
    (net (code "72") (name "Net-(Q22-B)") (class "Default")
      (node (ref "Q22") (pin "2") (pinfunction "B_2") (pintype "passive"))
      (node (ref "R45") (pin "2") (pinfunction "2_2") (pintype "passive"))
    )
    (net (code "73") (name "Net-(Q22-C)") (class "Default")
      (node (ref "P12") (pin "3") (pinfunction "3_3") (pintype "passive"))
      (node (ref "Q22") (pin "3") (pinfunction "C_3") (pintype "passive"))
      (node (ref "R42") (pin "2") (pinfunction "2_2") (pintype "passive"))
    )
    (net (code "74") (name "Net-(Q23-B)") (class "Default")
      (node (ref "Q23") (pin "2") (pinfunction "B_2") (pintype "passive"))
      (node (ref "R47") (pin "2") (pinfunction "2_2") (pintype "passive"))
    )
    (net (code "75") (name "Net-(Q23-C)") (class "Default")
      (node (ref "P13") (pin "3") (pinfunction "3_3") (pintype "passive"))
      (node (ref "Q23") (pin "3") (pinfunction "C_3") (pintype "passive"))
      (node (ref "R43") (pin "2") (pinfunction "2_2") (pintype "passive"))
    )
    (net (code "76") (name "Net-(Q24-B)") (class "Default")
      (node (ref "Q24") (pin "2") (pinfunction "B_2") (pintype "passive"))
      (node (ref "R48") (pin "2") (pinfunction "2_2") (pintype "passive"))
    )
    (net (code "77") (name "Net-(Q24-C)") (class "Default")
      (node (ref "P9") (pin "6") (pinfunction "6_6") (pintype "passive"))
      (node (ref "Q24") (pin "3") (pinfunction "C_3") (pintype "passive"))
      (node (ref "R46") (pin "2") (pinfunction "2_2") (pintype "passive"))
    )
    (net (code "78") (name "Net-(Q25-B)") (class "Default")
      (node (ref "Q25") (pin "2") (pinfunction "B_2") (pintype "passive"))
      (node (ref "R51") (pin "2") (pinfunction "2_2") (pintype "passive"))
    )
    (net (code "79") (name "Net-(Q25-C)") (class "Default")
      (node (ref "P12") (pin "4") (pinfunction "4_4") (pintype "passive"))
      (node (ref "Q25") (pin "3") (pinfunction "C_3") (pintype "passive"))
      (node (ref "R49") (pin "2") (pinfunction "2_2") (pintype "passive"))
    )
    (net (code "80") (name "Net-(Q26-B)") (class "Default")
      (node (ref "Q26") (pin "2") (pinfunction "B_2") (pintype "passive"))
      (node (ref "R52") (pin "2") (pinfunction "2_2") (pintype "passive"))
    )
    (net (code "81") (name "Net-(Q26-C)") (class "Default")
      (node (ref "P13") (pin "4") (pinfunction "4_4") (pintype "passive"))
      (node (ref "Q26") (pin "3") (pinfunction "C_3") (pintype "passive"))
      (node (ref "R50") (pin "2") (pinfunction "2_2") (pintype "passive"))
    )
  )
)
